# synapse_rpi3_adapter.net
KiCad netlist of a schematic drawn in EAGLE
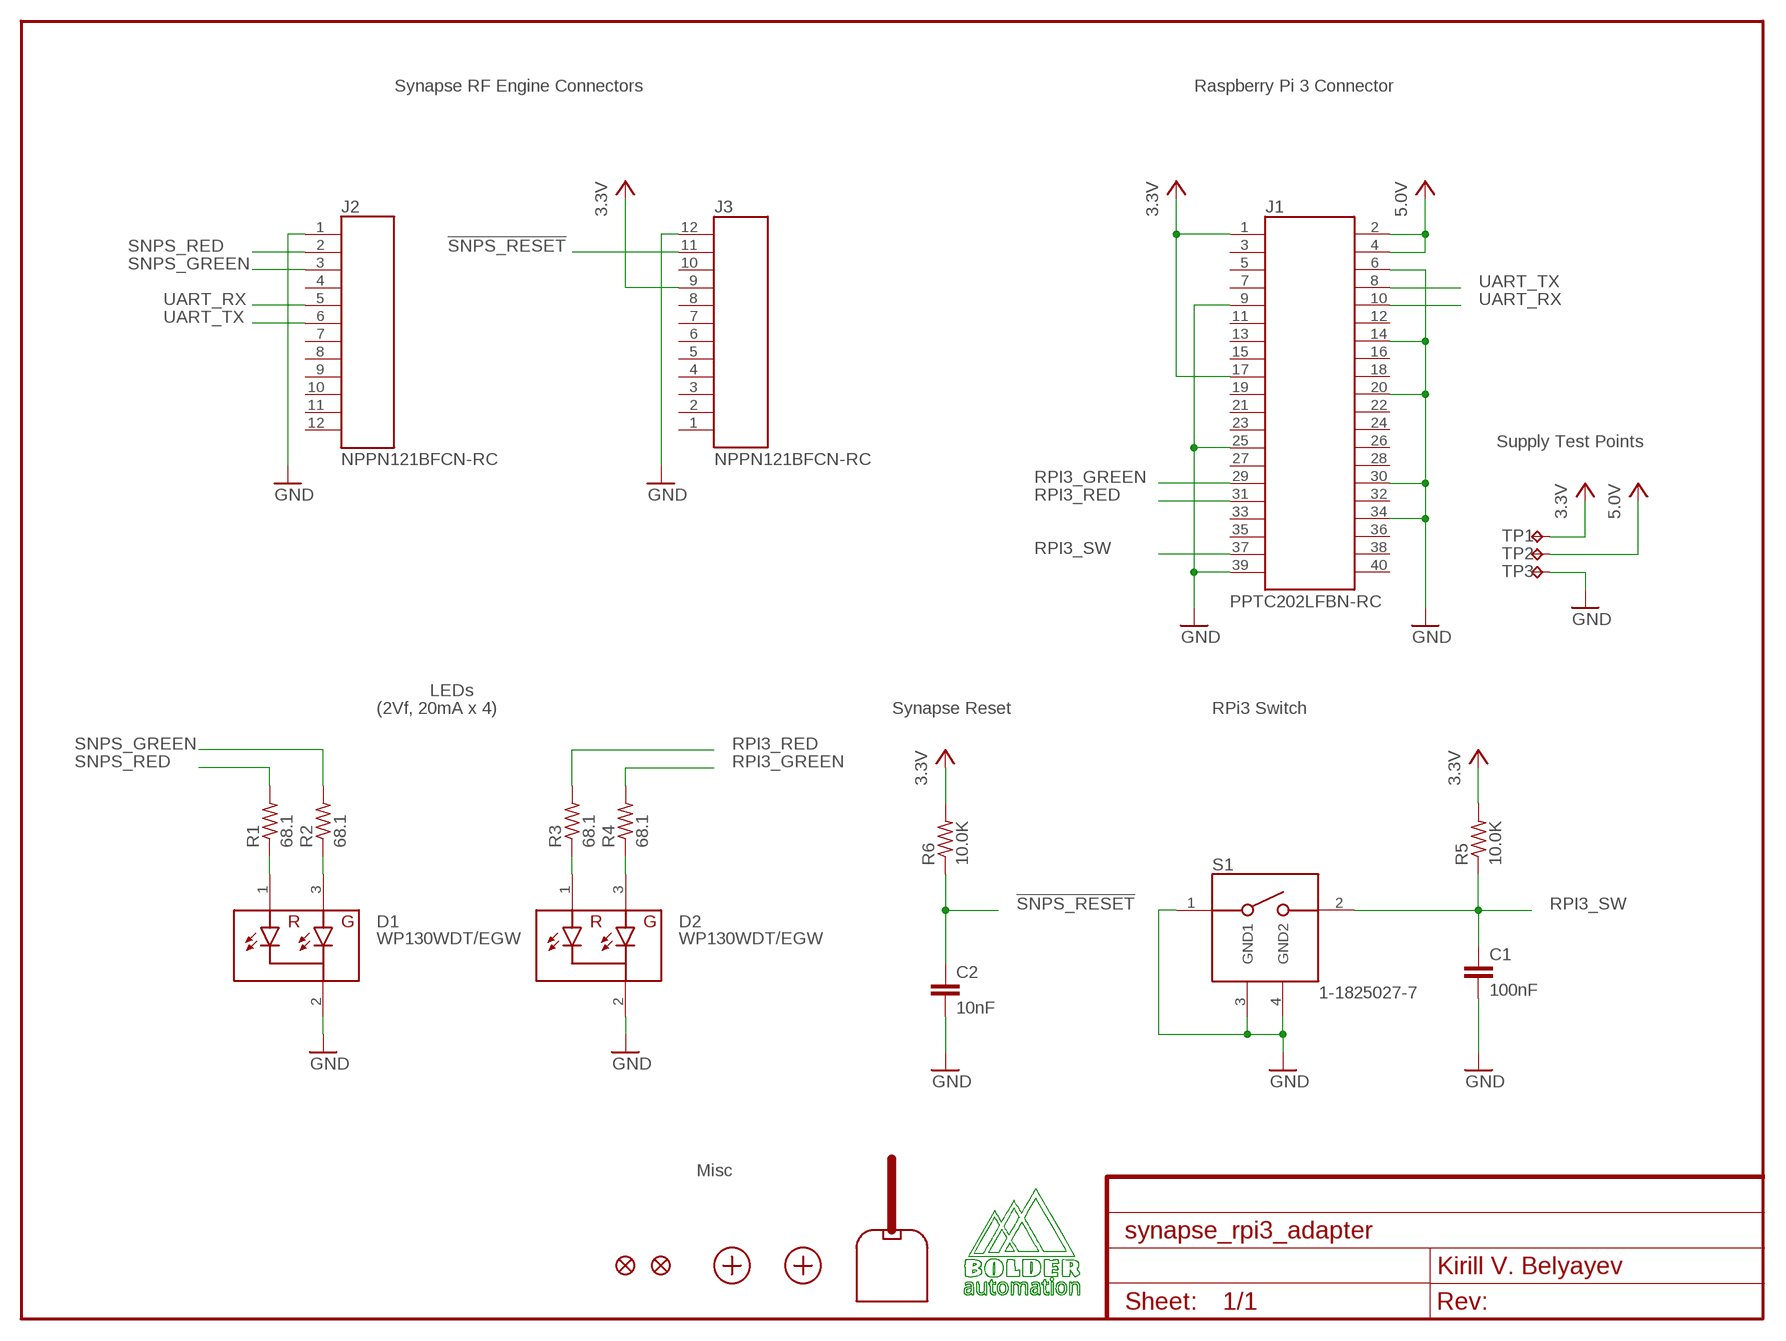
[diagram p0: schematic, sheet 1]

(export (version "E")
  (design (tool "Eeschema 10.0.6"))
  (components
    (comp (ref "C1")
      (value "100nF")
      (footprint "eagle-import:C0603")
      (libsource (lib "eagle-import") (part "C-EUC0603"))
    )
    (comp (ref "C2")
      (value "10nF")
      (footprint "eagle-import:C0603")
      (libsource (lib "eagle-import") (part "C-EUC0603"))
    )
    (comp (ref "D1")
      (value "WP130WDT/EGW")
      (footprint "eagle-import:WP130WDT_EGW")
      (fields (field (name "MANUFACTURER") "Kingbright"))
      (libsource (lib "eagle-import") (part "WP130WDT/EGW"))
    )
    (comp (ref "D2")
      (value "WP130WDT/EGW")
      (footprint "eagle-import:WP130WDT_EGW")
      (fields (field (name "MANUFACTURER") "Kingbright"))
      (libsource (lib "eagle-import") (part "WP130WDT/EGW"))
    )
    (comp (ref "FD1")
      (value "FIDUCIALUFIDUCIAL")
      (footprint "eagle-import:MICRO-FIDUCIAL")
      (libsource (lib "eagle-import") (part "FIDUCIALUFIDUCIAL"))
    )
    (comp (ref "FD2")
      (value "FIDUCIALUFIDUCIAL")
      (footprint "eagle-import:MICRO-FIDUCIAL")
      (libsource (lib "eagle-import") (part "FIDUCIALUFIDUCIAL"))
    )
    (comp (ref "J1")
      (value "PPTC202LFBN-RC")
      (footprint "eagle-import:PPTC202LFBN-RC")
      (fields (field (name "MANUFACTURER") "Sullins Connector Solutions"))
      (libsource (lib "eagle-import") (part "PPTC202LFBN-RC"))
    )
    (comp (ref "J2")
      (value "NPPN121BFCN-RC")
      (footprint "eagle-import:NPPN121BFCN-RC")
      (fields (field (name "MANUFACTURER") "Sullins Connector Solutions"))
      (libsource (lib "eagle-import") (part "NPPN121BFCN-RC"))
    )
    (comp (ref "J3")
      (value "NPPN121BFCN-RC")
      (footprint "eagle-import:NPPN121BFCN-RC")
      (fields (field (name "MANUFACTURER") "Sullins Connector Solutions"))
      (libsource (lib "eagle-import") (part "NPPN121BFCN-RC"))
    )
    (comp (ref "MNT1")
      (value "MOUNT-HOLE-NO-PLATE5.0MM")
      (footprint "eagle-import:MOUNT-HOLE-NO-PLATE-5.0MM")
      (libsource (lib "eagle-import") (part "MOUNT-HOLE-NO-PLATE5.0MM"))
    )
    (comp (ref "MNT2")
      (value "MOUNT-HOLE-NO-PLATE5.0MM")
      (footprint "eagle-import:MOUNT-HOLE-NO-PLATE-5.0MM")
      (libsource (lib "eagle-import") (part "MOUNT-HOLE-NO-PLATE5.0MM"))
    )
    (comp (ref "R1")
      (value "68.1")
      (footprint "eagle-import:R0603")
      (libsource (lib "eagle-import") (part "R-US_R0603"))
    )
    (comp (ref "R2")
      (value "68.1")
      (footprint "eagle-import:R0603")
      (libsource (lib "eagle-import") (part "R-US_R0603"))
    )
    (comp (ref "R3")
      (value "68.1")
      (footprint "eagle-import:R0603")
      (libsource (lib "eagle-import") (part "R-US_R0603"))
    )
    (comp (ref "R4")
      (value "68.1")
      (footprint "eagle-import:R0603")
      (libsource (lib "eagle-import") (part "R-US_R0603"))
    )
    (comp (ref "R5")
      (value "10.0K")
      (footprint "eagle-import:R0603")
      (libsource (lib "eagle-import") (part "R-US_R0603"))
    )
    (comp (ref "R6")
      (value "10.0K")
      (footprint "eagle-import:R0603")
      (libsource (lib "eagle-import") (part "R-US_R0603"))
    )
    (comp (ref "S1")
      (value "1-1825027-7")
      (footprint "eagle-import:1-1825027-7")
      (fields (field (name "MANUFACTURER") "TE Connectivity"))
      (libsource (lib "eagle-import") (part "1-1825027-7"))
    )
    (comp (ref "TP1")
      (value "TEST-POINT")
      (footprint "eagle-import:TEST-POINT-40MILL")
      (libsource (lib "eagle-import") (part "TEST-POINT"))
    )
    (comp (ref "TP2")
      (value "TEST-POINT")
      (footprint "eagle-import:TEST-POINT-40MILL")
      (libsource (lib "eagle-import") (part "TEST-POINT"))
    )
    (comp (ref "TP3")
      (value "TEST-POINT")
      (footprint "eagle-import:TEST-POINT-40MILL")
      (libsource (lib "eagle-import") (part "TEST-POINT"))
    )
    (comp (ref "U$1")
      (value "BA_LOGO")
      (footprint "eagle-import:BA_LOGO")
      (libsource (lib "eagle-import") (part "BA_LOGO"))
    )
    (comp (ref "X1")
      (value "RF200PD1")
      (footprint "eagle-import:RF200PD1")
      (fields (field (name "MANUFACTURER") "Synapse Wireless"))
      (libsource (lib "eagle-import") (part "RF200PD1"))
    )
  )
  (nets
    (net (code "1") (name "/RPI3_GREEN") (class "Default")
      (node (ref "J1") (pin "29") (pinfunction "29_29") (pintype "bidirectional"))
      (node (ref "R4") (pin "2") (pinfunction "2_2") (pintype "passive"))
    )
    (net (code "2") (name "/RPI3_RED") (class "Default")
      (node (ref "J1") (pin "31") (pinfunction "31_31") (pintype "bidirectional"))
      (node (ref "R3") (pin "2") (pinfunction "2_2") (pintype "passive"))
    )
    (net (code "3") (name "/RPI3_SW") (class "Default")
      (node (ref "C1") (pin "1") (pinfunction "1_1") (pintype "passive"))
      (node (ref "J1") (pin "37") (pinfunction "37_37") (pintype "bidirectional"))
      (node (ref "R5") (pin "1") (pinfunction "1_1") (pintype "passive"))
      (node (ref "S1") (pin "2") (pinfunction "P$2_2") (pintype "bidirectional"))
    )
    (net (code "4") (name "/SNPS_GREEN") (class "Default")
      (node (ref "J2") (pin "3") (pinfunction "P$3_3") (pintype "bidirectional"))
      (node (ref "R2") (pin "2") (pinfunction "2_2") (pintype "passive"))
    )
    (net (code "5") (name "/SNPS_RED") (class "Default")
      (node (ref "J2") (pin "2") (pinfunction "P$2_2") (pintype "bidirectional"))
      (node (ref "R1") (pin "2") (pinfunction "2_2") (pintype "passive"))
    )
    (net (code "6") (name "/UART_RX") (class "Default")
      (node (ref "J1") (pin "10") (pinfunction "10_10") (pintype "bidirectional"))
      (node (ref "J2") (pin "5") (pinfunction "P$5_5") (pintype "bidirectional"))
    )
    (net (code "7") (name "/UART_TX") (class "Default")
      (node (ref "J1") (pin "8") (pinfunction "8_8") (pintype "bidirectional"))
      (node (ref "J2") (pin "6") (pinfunction "P$6_6") (pintype "bidirectional"))
    )
    (net (code "8") (name "/~{SNPS_RESET}") (class "Default")
      (node (ref "C2") (pin "1") (pinfunction "1_1") (pintype "passive"))
      (node (ref "J3") (pin "11") (pinfunction "P$11_11") (pintype "bidirectional"))
      (node (ref "R6") (pin "1") (pinfunction "1_1") (pintype "passive"))
    )
    (net (code "9") (name "3.3V") (class "Default")
      (node (ref "J1") (pin "1") (pinfunction "1_1") (pintype "bidirectional"))
      (node (ref "J1") (pin "17") (pinfunction "17_17") (pintype "bidirectional"))
      (node (ref "J3") (pin "9") (pinfunction "P$9_9") (pintype "bidirectional"))
      (node (ref "R5") (pin "2") (pinfunction "2_2") (pintype "passive"))
      (node (ref "R6") (pin "2") (pinfunction "2_2") (pintype "passive"))
      (node (ref "TP1") (pin "1") (pinfunction "PP_1") (pintype "input"))
    )
    (net (code "10") (name "5.0V") (class "Default")
      (node (ref "J1") (pin "2") (pinfunction "2_2") (pintype "bidirectional"))
      (node (ref "J1") (pin "4") (pinfunction "4_4") (pintype "bidirectional"))
      (node (ref "TP2") (pin "1") (pinfunction "PP_1") (pintype "input"))
    )
    (net (code "11") (name "GND") (class "Default")
      (node (ref "C1") (pin "2") (pinfunction "2_2") (pintype "passive"))
      (node (ref "C2") (pin "2") (pinfunction "2_2") (pintype "passive"))
      (node (ref "D1") (pin "2") (pinfunction "P$2_2") (pintype "bidirectional"))
      (node (ref "D2") (pin "2") (pinfunction "P$2_2") (pintype "bidirectional"))
      (node (ref "J1") (pin "14") (pinfunction "14_14") (pintype "bidirectional"))
      (node (ref "J1") (pin "20") (pinfunction "20_20") (pintype "bidirectional"))
      (node (ref "J1") (pin "25") (pinfunction "25_25") (pintype "bidirectional"))
      (node (ref "J1") (pin "30") (pinfunction "30_30") (pintype "bidirectional"))
      (node (ref "J1") (pin "34") (pinfunction "34_34") (pintype "bidirectional"))
      (node (ref "J1") (pin "39") (pinfunction "39_39") (pintype "bidirectional"))
      (node (ref "J1") (pin "6") (pinfunction "6_6") (pintype "bidirectional"))
      (node (ref "J1") (pin "9") (pinfunction "9_9") (pintype "bidirectional"))
      (node (ref "J2") (pin "1") (pinfunction "P$1_1") (pintype "bidirectional"))
      (node (ref "J3") (pin "12") (pinfunction "P$12_12") (pintype "bidirectional"))
      (node (ref "S1") (pin "1") (pinfunction "P$1_1") (pintype "bidirectional"))
      (node (ref "S1") (pin "3") (pinfunction "GND1_3") (pintype "bidirectional"))
      (node (ref "S1") (pin "4") (pinfunction "GND2_4") (pintype "bidirectional"))
      (node (ref "TP3") (pin "1") (pinfunction "PP_1") (pintype "input"))
    )
    (net (code "12") (name "Net-(D1-GRN)") (class "Default")
      (node (ref "D1") (pin "3") (pinfunction "GRN_3") (pintype "bidirectional"))
      (node (ref "R2") (pin "1") (pinfunction "1_1") (pintype "passive"))
    )
    (net (code "13") (name "Net-(D1-RED)") (class "Default")
      (node (ref "D1") (pin "1") (pinfunction "RED_1") (pintype "bidirectional"))
      (node (ref "R1") (pin "1") (pinfunction "1_1") (pintype "passive"))
    )
    (net (code "14") (name "Net-(D2-GRN)") (class "Default")
      (node (ref "D2") (pin "3") (pinfunction "GRN_3") (pintype "bidirectional"))
      (node (ref "R4") (pin "1") (pinfunction "1_1") (pintype "passive"))
    )
    (net (code "15") (name "Net-(D2-RED)") (class "Default")
      (node (ref "D2") (pin "1") (pinfunction "RED_1") (pintype "bidirectional"))
      (node (ref "R3") (pin "1") (pinfunction "1_1") (pintype "passive"))
    )
    (net (code "16") (name "unconnected-(J1-Pad3)") (class "Default")
      (node (ref "J1") (pin "3") (pinfunction "3_3") (pintype "bidirectional"))
    )
    (net (code "17") (name "unconnected-(J1-Pad5)") (class "Default")
      (node (ref "J1") (pin "5") (pinfunction "5_5") (pintype "bidirectional"))
    )
    (net (code "18") (name "unconnected-(J1-Pad7)") (class "Default")
      (node (ref "J1") (pin "7") (pinfunction "7_7") (pintype "bidirectional"))
    )
    (net (code "19") (name "unconnected-(J1-Pad11)") (class "Default")
      (node (ref "J1") (pin "11") (pinfunction "11_11") (pintype "bidirectional"))
    )
    (net (code "20") (name "unconnected-(J1-Pad12)") (class "Default")
      (node (ref "J1") (pin "12") (pinfunction "12_12") (pintype "bidirectional"))
    )
    (net (code "21") (name "unconnected-(J1-Pad13)") (class "Default")
      (node (ref "J1") (pin "13") (pinfunction "13_13") (pintype "bidirectional"))
    )
    (net (code "22") (name "unconnected-(J1-Pad15)") (class "Default")
      (node (ref "J1") (pin "15") (pinfunction "15_15") (pintype "bidirectional"))
    )
    (net (code "23") (name "unconnected-(J1-Pad16)") (class "Default")
      (node (ref "J1") (pin "16") (pinfunction "16_16") (pintype "bidirectional"))
    )
    (net (code "24") (name "unconnected-(J1-Pad18)") (class "Default")
      (node (ref "J1") (pin "18") (pinfunction "18_18") (pintype "bidirectional"))
    )
    (net (code "25") (name "unconnected-(J1-Pad19)") (class "Default")
      (node (ref "J1") (pin "19") (pinfunction "19_19") (pintype "bidirectional"))
    )
    (net (code "26") (name "unconnected-(J1-Pad21)") (class "Default")
      (node (ref "J1") (pin "21") (pinfunction "21_21") (pintype "bidirectional"))
    )
    (net (code "27") (name "unconnected-(J1-Pad22)") (class "Default")
      (node (ref "J1") (pin "22") (pinfunction "22_22") (pintype "bidirectional"))
    )
    (net (code "28") (name "unconnected-(J1-Pad23)") (class "Default")
      (node (ref "J1") (pin "23") (pinfunction "23_23") (pintype "bidirectional"))
    )
    (net (code "29") (name "unconnected-(J1-Pad24)") (class "Default")
      (node (ref "J1") (pin "24") (pinfunction "24_24") (pintype "bidirectional"))
    )
    (net (code "30") (name "unconnected-(J1-Pad26)") (class "Default")
      (node (ref "J1") (pin "26") (pinfunction "26_26") (pintype "bidirectional"))
    )
    (net (code "31") (name "unconnected-(J1-Pad27)") (class "Default")
      (node (ref "J1") (pin "27") (pinfunction "27_27") (pintype "bidirectional"))
    )
    (net (code "32") (name "unconnected-(J1-Pad28)") (class "Default")
      (node (ref "J1") (pin "28") (pinfunction "28_28") (pintype "bidirectional"))
    )
    (net (code "33") (name "unconnected-(J1-Pad32)") (class "Default")
      (node (ref "J1") (pin "32") (pinfunction "32_32") (pintype "bidirectional"))
    )
    (net (code "34") (name "unconnected-(J1-Pad33)") (class "Default")
      (node (ref "J1") (pin "33") (pinfunction "33_33") (pintype "bidirectional"))
    )
    (net (code "35") (name "unconnected-(J1-Pad35)") (class "Default")
      (node (ref "J1") (pin "35") (pinfunction "35_35") (pintype "bidirectional"))
    )
    (net (code "36") (name "unconnected-(J1-Pad36)") (class "Default")
      (node (ref "J1") (pin "36") (pinfunction "36_36") (pintype "bidirectional"))
    )
    (net (code "37") (name "unconnected-(J1-Pad38)") (class "Default")
      (node (ref "J1") (pin "38") (pinfunction "38_38") (pintype "bidirectional"))
    )
    (net (code "38") (name "unconnected-(J1-Pad40)") (class "Default")
      (node (ref "J1") (pin "40") (pinfunction "40_40") (pintype "bidirectional"))
    )
    (net (code "39") (name "unconnected-(J2-P$4-Pad4)") (class "Default")
      (node (ref "J2") (pin "4") (pinfunction "P$4_4") (pintype "bidirectional"))
    )
    (net (code "40") (name "unconnected-(J2-P$7-Pad7)") (class "Default")
      (node (ref "J2") (pin "7") (pinfunction "P$7_7") (pintype "bidirectional"))
    )
    (net (code "41") (name "unconnected-(J2-P$8-Pad8)") (class "Default")
      (node (ref "J2") (pin "8") (pinfunction "P$8_8") (pintype "bidirectional"))
    )
    (net (code "42") (name "unconnected-(J2-P$9-Pad9)") (class "Default")
      (node (ref "J2") (pin "9") (pinfunction "P$9_9") (pintype "bidirectional"))
    )
    (net (code "43") (name "unconnected-(J2-P$10-Pad10)") (class "Default")
      (node (ref "J2") (pin "10") (pinfunction "P$10_10") (pintype "bidirectional"))
    )
    (net (code "44") (name "unconnected-(J2-P$11-Pad11)") (class "Default")
      (node (ref "J2") (pin "11") (pinfunction "P$11_11") (pintype "bidirectional"))
    )
    (net (code "45") (name "unconnected-(J2-P$12-Pad12)") (class "Default")
      (node (ref "J2") (pin "12") (pinfunction "P$12_12") (pintype "bidirectional"))
    )
    (net (code "46") (name "unconnected-(J3-P$1-Pad1)") (class "Default")
      (node (ref "J3") (pin "1") (pinfunction "P$1_1") (pintype "bidirectional"))
    )
    (net (code "47") (name "unconnected-(J3-P$2-Pad2)") (class "Default")
      (node (ref "J3") (pin "2") (pinfunction "P$2_2") (pintype "bidirectional"))
    )
    (net (code "48") (name "unconnected-(J3-P$3-Pad3)") (class "Default")
      (node (ref "J3") (pin "3") (pinfunction "P$3_3") (pintype "bidirectional"))
    )
    (net (code "49") (name "unconnected-(J3-P$4-Pad4)") (class "Default")
      (node (ref "J3") (pin "4") (pinfunction "P$4_4") (pintype "bidirectional"))
    )
    (net (code "50") (name "unconnected-(J3-P$5-Pad5)") (class "Default")
      (node (ref "J3") (pin "5") (pinfunction "P$5_5") (pintype "bidirectional"))
    )
    (net (code "51") (name "unconnected-(J3-P$6-Pad6)") (class "Default")
      (node (ref "J3") (pin "6") (pinfunction "P$6_6") (pintype "bidirectional"))
    )
    (net (code "52") (name "unconnected-(J3-P$7-Pad7)") (class "Default")
      (node (ref "J3") (pin "7") (pinfunction "P$7_7") (pintype "bidirectional"))
    )
    (net (code "53") (name "unconnected-(J3-P$8-Pad8)") (class "Default")
      (node (ref "J3") (pin "8") (pinfunction "P$8_8") (pintype "bidirectional"))
    )
    (net (code "54") (name "unconnected-(J3-P$10-Pad10)") (class "Default")
      (node (ref "J3") (pin "10") (pinfunction "P$10_10") (pintype "bidirectional"))
    )
  )
)
